# ILI9341_4Wire.net
KiCad netlist of a schematic drawn in Altium Designer
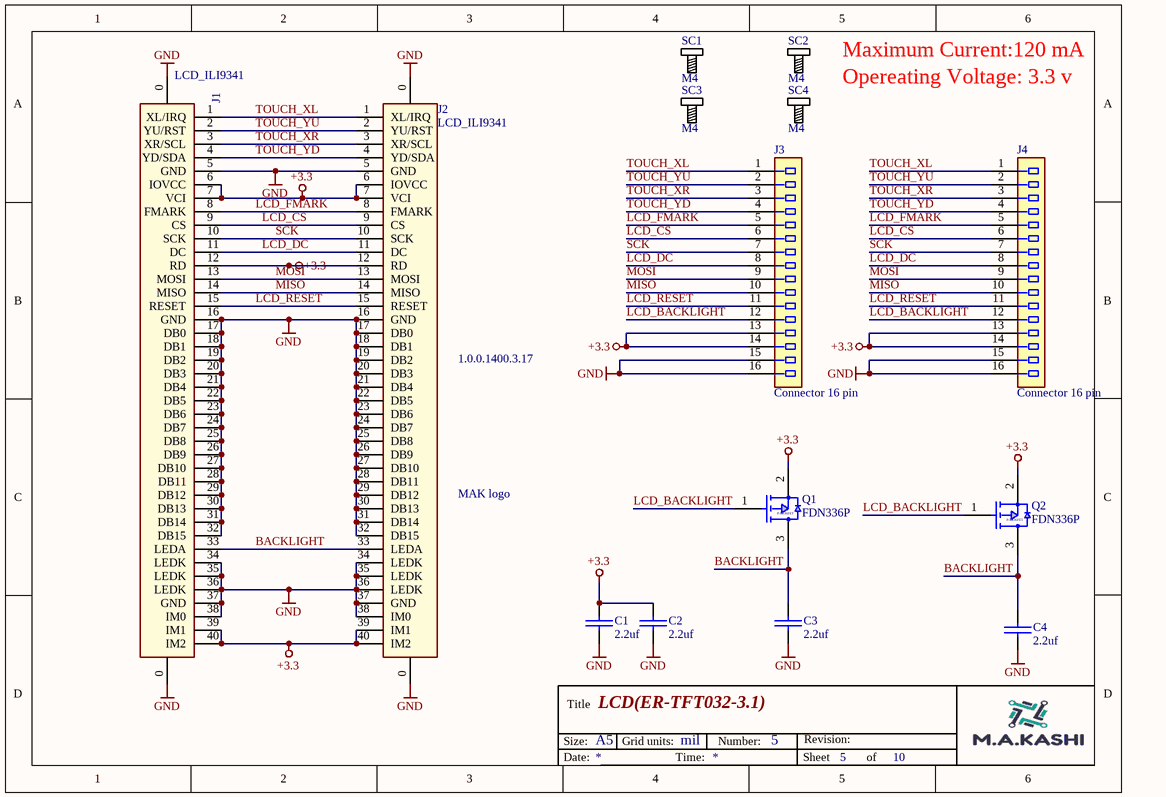
[diagram p0: ILI9341_4Wire.SchDoc]

(export (version "E")
  (design (tool "Eeschema 10.0.6"))
  (components
    (comp (ref "1.0.0.1400.3.17")
      (value "MAK logo")
      (footprint "MAk LOGO")
      (libsource (lib "E-component") (part "MAK logo"))
    )
    (comp (ref "C1")
      (value "2.2uf")
      (footprint "cap_0805_B")
      (description "octopart or digikey description!")
      (fields (field (name "PART NUMBER") "C0402X7R160-104KNE"))
      (libsource (lib "E-component") (part "Capacitor"))
    )
    (comp (ref "C2")
      (value "2.2uf")
      (footprint "cap_0805_B")
      (description "octopart or digikey description!")
      (fields (field (name "PART NUMBER") "C0402X7R160-104KNE"))
      (libsource (lib "E-component") (part "Capacitor"))
    )
    (comp (ref "C3")
      (value "2.2uf")
      (footprint "cap_0805_B")
      (description "octopart or digikey description!")
      (fields (field (name "PART NUMBER") "CL21A106KOQNNNG"))
      (libsource (lib "E-component") (part "Capacitor"))
    )
    (comp (ref "C4")
      (value "2.2uf")
      (footprint "cap_0805_B")
      (description "octopart or digikey description!")
      (fields (field (name "PART NUMBER") "CL21A106KOQNNNG"))
      (libsource (lib "E-component") (part "Capacitor"))
    )
    (comp (ref "J1")
      (value "LCD_ILI9341")
      (footprint "FPC 40 - top")
      (description "50pin FPC connector, 0.5mm pitch, Top/Bottom contacts")
      (fields (field (name "MANUFACTURER") "Omron Components") (field (name "MPN") "XF2M-5015-1A"))
      (libsource (lib "E-component") (part "LCD_ILI9341"))
    )
    (comp (ref "J2")
      (value "LCD_ILI9341")
      (footprint "FPC 40 - bottom")
      (description "50pin FPC connector, 0.5mm pitch, Top/Bottom contacts")
      (fields (field (name "MANUFACTURER") "Omron Components") (field (name "MPN") "XF2M-5015-1A"))
      (libsource (lib "") (part "LCD_ILI9341_1"))
    )
    (comp (ref "J3")
      (value "Connector 16 pin")
      (footprint "DS1013-16S - with Latch/Eject Levers")
      (libsource (lib "E-component") (part "Connector 16 pin"))
    )
    (comp (ref "J4")
      (value "Connector 16 pin")
      (footprint "DS1013-16S - with Latch/Eject Levers")
      (libsource (lib "E-component") (part "Connector 16 pin"))
    )
    (comp (ref "Q1")
      (value "FDN336P")
      (footprint "Diodes_Inc_SOT23_IPC_A")
      (fields (field (name "PART NUMBER") "DMP3099L-13"))
      (libsource (lib "E-component") (part "DMP3099L-13_1"))
    )
    (comp (ref "Q2")
      (value "FDN336P")
      (footprint "Diodes_Inc_SOT23_IPC_A")
      (fields (field (name "PART NUMBER") "DMP3099L-13"))
      (libsource (lib "E-component") (part "DMP3099L-13_1"))
    )
    (comp (ref "SC1")
      (value "M4")
      (footprint "SCREW_M4")
      (description "Screw")
      (libsource (lib "E-component") (part "Screw_M4"))
    )
    (comp (ref "SC2")
      (value "M4")
      (footprint "SCREW_M4")
      (description "Screw")
      (libsource (lib "E-component") (part "Screw_M4"))
    )
    (comp (ref "SC3")
      (value "M4")
      (footprint "SCREW_M4")
      (description "Screw")
      (libsource (lib "E-component") (part "Screw_M4"))
    )
    (comp (ref "SC4")
      (value "M4")
      (footprint "SCREW_M4")
      (description "Screw")
      (libsource (lib "E-component") (part "Screw_M4"))
    )
  )
  (nets
    (net (code "1") (name "+3.3") (class "Default")
      (node (ref "C1") (pin "2") (pinfunction "2_2") (pintype "passive"))
      (node (ref "C2") (pin "2") (pinfunction "2_2") (pintype "passive"))
      (node (ref "J1") (pin "12") (pinfunction "RD_12") (pintype "passive"))
      (node (ref "J1") (pin "39") (pinfunction "IM1_39") (pintype "passive"))
      (node (ref "J1") (pin "40") (pinfunction "IM2_40") (pintype "passive"))
      (node (ref "J1") (pin "6") (pinfunction "IOVCC_6") (pintype "passive"))
      (node (ref "J1") (pin "7") (pinfunction "VCI_7") (pintype "passive"))
      (node (ref "J2") (pin "12") (pinfunction "RD_12") (pintype "passive"))
      (node (ref "J2") (pin "39") (pinfunction "IM1_39") (pintype "passive"))
      (node (ref "J2") (pin "40") (pinfunction "IM2_40") (pintype "passive"))
      (node (ref "J2") (pin "6") (pinfunction "IOVCC_6") (pintype "passive"))
      (node (ref "J2") (pin "7") (pinfunction "VCI_7") (pintype "passive"))
      (node (ref "J3") (pin "13") (pinfunction "13_13") (pintype "passive"))
      (node (ref "J3") (pin "14") (pinfunction "14_14") (pintype "passive"))
      (node (ref "J4") (pin "13") (pinfunction "13_13") (pintype "passive"))
      (node (ref "J4") (pin "14") (pinfunction "14_14") (pintype "passive"))
      (node (ref "Q1") (pin "2") (pinfunction "S_2") (pintype "passive"))
      (node (ref "Q2") (pin "2") (pinfunction "S_2") (pintype "passive"))
    )
    (net (code "2") (name "/BACKLIGHT") (class "Default")
      (node (ref "C3") (pin "1") (pinfunction "1_1") (pintype "passive"))
      (node (ref "C4") (pin "1") (pinfunction "1_1") (pintype "passive"))
      (node (ref "J1") (pin "33") (pinfunction "LEDA_33") (pintype "passive"))
      (node (ref "J2") (pin "33") (pinfunction "LEDA_33") (pintype "passive"))
      (node (ref "Q1") (pin "3") (pinfunction "D_3") (pintype "passive"))
      (node (ref "Q2") (pin "3") (pinfunction "D_3") (pintype "passive"))
    )
    (net (code "3") (name "/LCD_BACKLIGHT") (class "Default")
      (node (ref "J3") (pin "12") (pinfunction "12_12") (pintype "passive"))
      (node (ref "J4") (pin "12") (pinfunction "12_12") (pintype "passive"))
      (node (ref "Q1") (pin "1") (pinfunction "G_1") (pintype "passive"))
      (node (ref "Q2") (pin "1") (pinfunction "G_1") (pintype "passive"))
    )
    (net (code "4") (name "/LCD_CS") (class "Default")
      (node (ref "J1") (pin "9") (pinfunction "CS_9") (pintype "passive"))
      (node (ref "J2") (pin "9") (pinfunction "CS_9") (pintype "passive"))
      (node (ref "J3") (pin "6") (pinfunction "6_6") (pintype "passive"))
      (node (ref "J4") (pin "6") (pinfunction "6_6") (pintype "passive"))
    )
    (net (code "5") (name "/LCD_DC") (class "Default")
      (node (ref "J1") (pin "11") (pinfunction "DC_11") (pintype "passive"))
      (node (ref "J2") (pin "11") (pinfunction "DC_11") (pintype "passive"))
      (node (ref "J3") (pin "8") (pinfunction "8_8") (pintype "passive"))
      (node (ref "J4") (pin "8") (pinfunction "8_8") (pintype "passive"))
    )
    (net (code "6") (name "/LCD_FMARK") (class "Default")
      (node (ref "J1") (pin "8") (pinfunction "FMARK_8") (pintype "passive"))
      (node (ref "J2") (pin "8") (pinfunction "FMARK_8") (pintype "passive"))
      (node (ref "J3") (pin "5") (pinfunction "5_5") (pintype "passive"))
      (node (ref "J4") (pin "5") (pinfunction "5_5") (pintype "passive"))
    )
    (net (code "7") (name "/LCD_RESET") (class "Default")
      (node (ref "J1") (pin "15") (pinfunction "RESET_15") (pintype "passive"))
      (node (ref "J2") (pin "15") (pinfunction "RESET_15") (pintype "passive"))
      (node (ref "J3") (pin "11") (pinfunction "11_11") (pintype "passive"))
      (node (ref "J4") (pin "11") (pinfunction "11_11") (pintype "passive"))
    )
    (net (code "8") (name "/MISO") (class "Default")
      (node (ref "J1") (pin "14") (pinfunction "MISO_14") (pintype "passive"))
      (node (ref "J2") (pin "14") (pinfunction "MISO_14") (pintype "passive"))
      (node (ref "J3") (pin "10") (pinfunction "10_10") (pintype "passive"))
      (node (ref "J4") (pin "10") (pinfunction "10_10") (pintype "passive"))
    )
    (net (code "9") (name "/MOSI") (class "Default")
      (node (ref "J1") (pin "13") (pinfunction "MOSI_13") (pintype "passive"))
      (node (ref "J2") (pin "13") (pinfunction "MOSI_13") (pintype "passive"))
      (node (ref "J3") (pin "9") (pinfunction "9_9") (pintype "passive"))
      (node (ref "J4") (pin "9") (pinfunction "9_9") (pintype "passive"))
    )
    (net (code "10") (name "/SCK") (class "Default")
      (node (ref "J1") (pin "10") (pinfunction "SCK_10") (pintype "passive"))
      (node (ref "J2") (pin "10") (pinfunction "SCK_10") (pintype "passive"))
      (node (ref "J3") (pin "7") (pinfunction "7_7") (pintype "passive"))
      (node (ref "J4") (pin "7") (pinfunction "7_7") (pintype "passive"))
    )
    (net (code "11") (name "/TOUCH_XL") (class "Default")
      (node (ref "J1") (pin "1") (pinfunction "XL/IRQ_1") (pintype "passive"))
      (node (ref "J2") (pin "1") (pinfunction "XL/IRQ_1") (pintype "passive"))
      (node (ref "J3") (pin "1") (pinfunction "1_1") (pintype "passive"))
      (node (ref "J4") (pin "1") (pinfunction "1_1") (pintype "passive"))
    )
    (net (code "12") (name "/TOUCH_XR") (class "Default")
      (node (ref "J1") (pin "3") (pinfunction "XR/SCL_3") (pintype "passive"))
      (node (ref "J2") (pin "3") (pinfunction "XR/SCL_3") (pintype "passive"))
      (node (ref "J3") (pin "3") (pinfunction "3_3") (pintype "passive"))
      (node (ref "J4") (pin "3") (pinfunction "3_3") (pintype "passive"))
    )
    (net (code "13") (name "/TOUCH_YD") (class "Default")
      (node (ref "J1") (pin "4") (pinfunction "YD/SDA_4") (pintype "passive"))
      (node (ref "J2") (pin "4") (pinfunction "YD/SDA_4") (pintype "passive"))
      (node (ref "J3") (pin "4") (pinfunction "4_4") (pintype "passive"))
      (node (ref "J4") (pin "4") (pinfunction "4_4") (pintype "passive"))
    )
    (net (code "14") (name "/TOUCH_YU") (class "Default")
      (node (ref "J1") (pin "2") (pinfunction "YU/RST_2") (pintype "passive"))
      (node (ref "J2") (pin "2") (pinfunction "YU/RST_2") (pintype "passive"))
      (node (ref "J3") (pin "2") (pinfunction "2_2") (pintype "passive"))
      (node (ref "J4") (pin "2") (pinfunction "2_2") (pintype "passive"))
    )
    (net (code "15") (name "GND") (class "Default")
      (node (ref "C1") (pin "1") (pinfunction "1_1") (pintype "passive"))
      (node (ref "C2") (pin "1") (pinfunction "1_1") (pintype "passive"))
      (node (ref "C3") (pin "2") (pinfunction "2_2") (pintype "passive"))
      (node (ref "C4") (pin "2") (pinfunction "2_2") (pintype "passive"))
      (node (ref "J1") (pin "0") (pinfunction "1_0") (pintype "passive"))
      (node (ref "J1") (pin "16") (pinfunction "GND_16") (pintype "passive"))
      (node (ref "J1") (pin "17") (pinfunction "DB0_17") (pintype "passive"))
      (node (ref "J1") (pin "18") (pinfunction "DB1_18") (pintype "passive"))
      (node (ref "J1") (pin "19") (pinfunction "DB2_19") (pintype "passive"))
      (node (ref "J1") (pin "20") (pinfunction "DB3_20") (pintype "passive"))
      (node (ref "J1") (pin "21") (pinfunction "DB4_21") (pintype "passive"))
      (node (ref "J1") (pin "22") (pinfunction "DB5_22") (pintype "passive"))
      (node (ref "J1") (pin "23") (pinfunction "DB6_23") (pintype "passive"))
      (node (ref "J1") (pin "24") (pinfunction "DB7_24") (pintype "passive"))
      (node (ref "J1") (pin "25") (pinfunction "DB8_25") (pintype "passive"))
      (node (ref "J1") (pin "26") (pinfunction "DB9_26") (pintype "passive"))
      (node (ref "J1") (pin "27") (pinfunction "DB10_27") (pintype "passive"))
      (node (ref "J1") (pin "28") (pinfunction "DB11_28") (pintype "passive"))
      (node (ref "J1") (pin "29") (pinfunction "DB12_29") (pintype "passive"))
      (node (ref "J1") (pin "30") (pinfunction "DB13_30") (pintype "passive"))
      (node (ref "J1") (pin "31") (pinfunction "DB14_31") (pintype "passive"))
      (node (ref "J1") (pin "32") (pinfunction "DB15_32") (pintype "passive"))
      (node (ref "J1") (pin "34") (pinfunction "LEDK_34") (pintype "passive"))
      (node (ref "J1") (pin "35") (pinfunction "LEDK_35") (pintype "passive"))
      (node (ref "J1") (pin "36") (pinfunction "LEDK_36") (pintype "passive"))
      (node (ref "J1") (pin "37") (pinfunction "GND_37") (pintype "passive"))
      (node (ref "J1") (pin "38") (pinfunction "IM0_38") (pintype "passive"))
      (node (ref "J1") (pin "5") (pinfunction "GND_5") (pintype "passive"))
      (node (ref "J2") (pin "0") (pinfunction "1_0") (pintype "passive"))
      (node (ref "J2") (pin "16") (pinfunction "GND_16") (pintype "passive"))
      (node (ref "J2") (pin "17") (pinfunction "DB0_17") (pintype "passive"))
      (node (ref "J2") (pin "18") (pinfunction "DB1_18") (pintype "passive"))
      (node (ref "J2") (pin "19") (pinfunction "DB2_19") (pintype "passive"))
      (node (ref "J2") (pin "20") (pinfunction "DB3_20") (pintype "passive"))
      (node (ref "J2") (pin "21") (pinfunction "DB4_21") (pintype "passive"))
      (node (ref "J2") (pin "22") (pinfunction "DB5_22") (pintype "passive"))
      (node (ref "J2") (pin "23") (pinfunction "DB6_23") (pintype "passive"))
      (node (ref "J2") (pin "24") (pinfunction "DB7_24") (pintype "passive"))
      (node (ref "J2") (pin "25") (pinfunction "DB8_25") (pintype "passive"))
      (node (ref "J2") (pin "26") (pinfunction "DB9_26") (pintype "passive"))
      (node (ref "J2") (pin "27") (pinfunction "DB10_27") (pintype "passive"))
      (node (ref "J2") (pin "28") (pinfunction "DB11_28") (pintype "passive"))
      (node (ref "J2") (pin "29") (pinfunction "DB12_29") (pintype "passive"))
      (node (ref "J2") (pin "30") (pinfunction "DB13_30") (pintype "passive"))
      (node (ref "J2") (pin "31") (pinfunction "DB14_31") (pintype "passive"))
      (node (ref "J2") (pin "32") (pinfunction "DB15_32") (pintype "passive"))
      (node (ref "J2") (pin "34") (pinfunction "LEDK_34") (pintype "passive"))
      (node (ref "J2") (pin "35") (pinfunction "LEDK_35") (pintype "passive"))
      (node (ref "J2") (pin "36") (pinfunction "LEDK_36") (pintype "passive"))
      (node (ref "J2") (pin "37") (pinfunction "GND_37") (pintype "passive"))
      (node (ref "J2") (pin "38") (pinfunction "IM0_38") (pintype "passive"))
      (node (ref "J2") (pin "5") (pinfunction "GND_5") (pintype "passive"))
      (node (ref "J3") (pin "15") (pinfunction "15_15") (pintype "passive"))
      (node (ref "J3") (pin "16") (pinfunction "16_16") (pintype "passive"))
      (node (ref "J4") (pin "15") (pinfunction "15_15") (pintype "passive"))
      (node (ref "J4") (pin "16") (pinfunction "16_16") (pintype "passive"))
    )
  )
)
